# 7_esc.net
KiCad netlist of a schematic drawn in Altium Designer
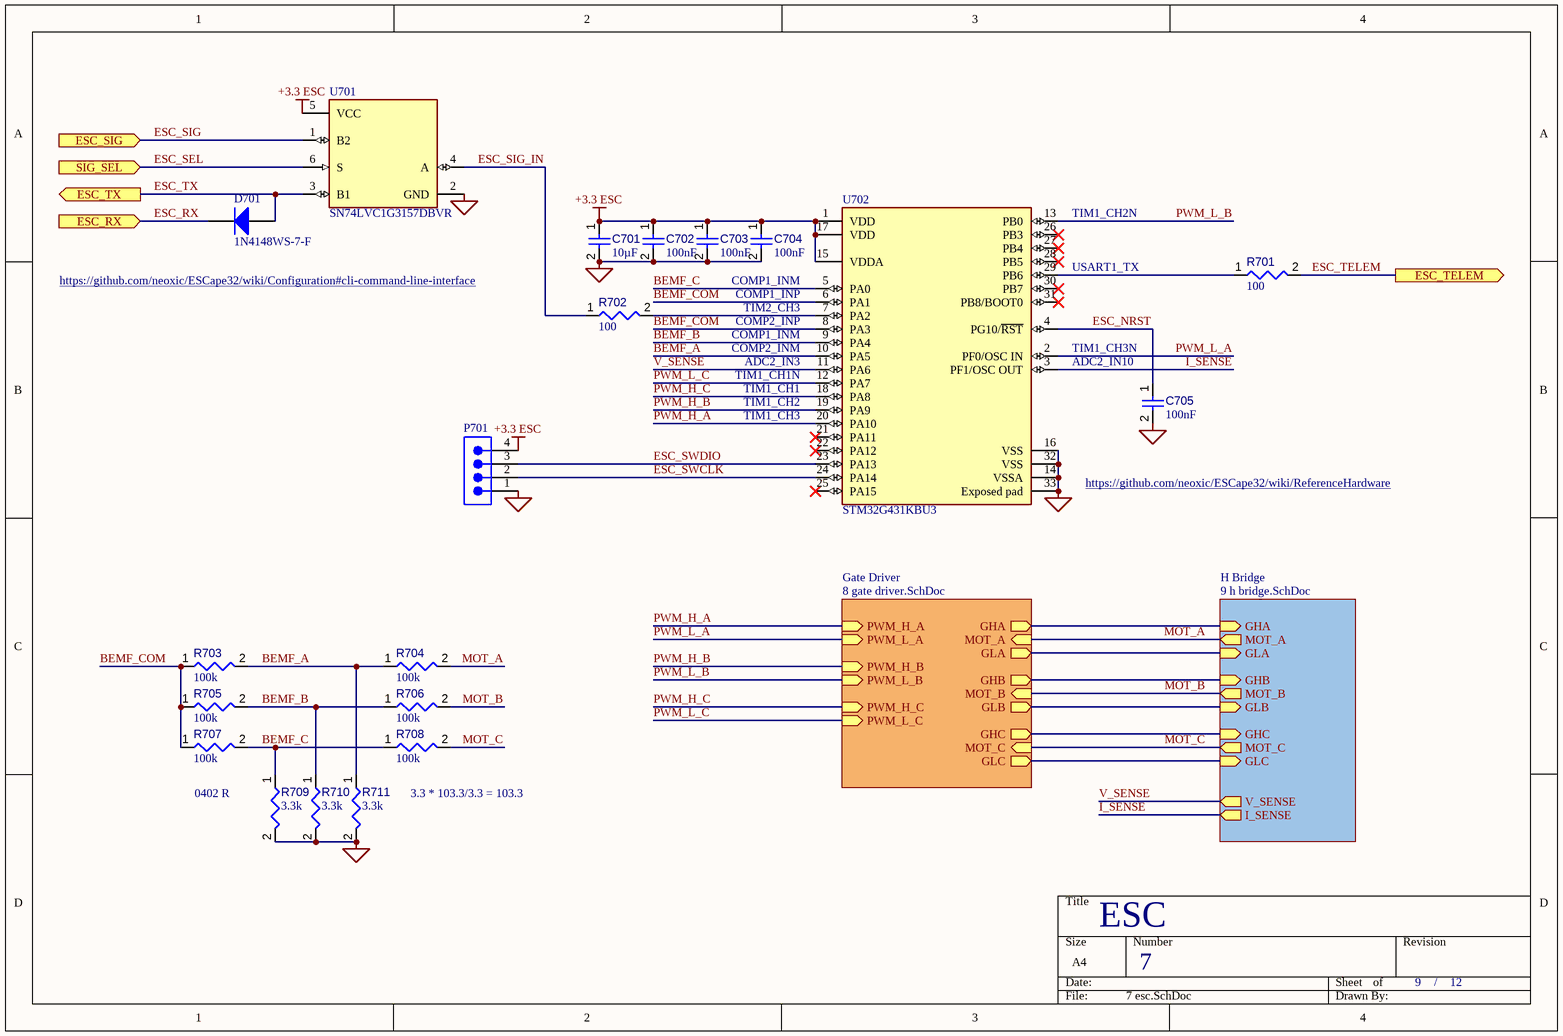
[diagram p0: 7 esc.SchDoc]

(export (version "E")
  (design (tool "Eeschema 10.0.6"))
  (components
    (comp (ref "C701")
      (value "10µF")
      (footprint "CAPC0603(1608)100_L")
      (description "Chip Capacitor, 10µF +/-20%, 10V, 0603, Thickness 1 mm")
      (fields (field (name "TOLERANCE") "10%") (field (name "Comment") "Capacitor 10µF +/-20% 10V 0603"))
      (libsource (lib "UBC Uncrewed Aircraft Systems") (part "CAP-NP-2"))
    )
    (comp (ref "C702")
      (value "100nF")
      (footprint "CAPC0402(1005)60_L")
      (description "Chip Capacitor, 100nF +/-20%, 25V, 0402, Thickness 0.6 mm")
      (fields (field (name "TOLERANCE") "10%") (field (name "Comment") "Capacitor 100nF +/-20% 25V 0402"))
      (libsource (lib "UBC Uncrewed Aircraft Systems") (part "CAP-NP-2"))
    )
    (comp (ref "C703")
      (value "100nF")
      (footprint "CAPC0402(1005)60_L")
      (description "Chip Capacitor, 100nF +/-20%, 25V, 0402, Thickness 0.6 mm")
      (fields (field (name "TOLERANCE") "10%") (field (name "Comment") "Capacitor 100nF +/-20% 25V 0402"))
      (libsource (lib "UBC Uncrewed Aircraft Systems") (part "CAP-NP-2"))
    )
    (comp (ref "C704")
      (value "100nF")
      (footprint "CAPC0402(1005)60_L")
      (description "Chip Capacitor, 100nF +/-20%, 25V, 0402, Thickness 0.6 mm")
      (fields (field (name "TOLERANCE") "10%") (field (name "Comment") "Capacitor 100nF +/-20% 25V 0402"))
      (libsource (lib "UBC Uncrewed Aircraft Systems") (part "CAP-NP-2"))
    )
    (comp (ref "C705")
      (value "100nF")
      (footprint "CAPC0402(1005)60_L")
      (description "Chip Capacitor, 100nF +/-20%, 25V, 0402, Thickness 0.6 mm")
      (fields (field (name "TOLERANCE") "10%") (field (name "Comment") "Capacitor 100nF +/-20% 25V 0402"))
      (libsource (lib "UBC Uncrewed Aircraft Systems") (part "CAP-NP-2"))
    )
    (comp (ref "D701")
      (value "1N4148WS-7-F")
      (footprint "DIOD-SOD323-2-A_V")
      (description "Fast Switching Diode, 75 V, 0.3 A, -65 to 150 degC, 2-Pin SOD323, RoHS, Tape and Reel")
      (libsource (lib "Altium Content Vault") (part "D-AK-2"))
    )
    (comp (ref "P701")
      (value "61300411121")
      (footprint "61300411121")
      (libsource (lib "Altium Content Vault") (part "Header_Male_1R_04P"))
    )
    (comp (ref "R701")
      (value "100")
      (footprint "RESC0402(1005)_L")
      (description "Chip Resistor, 100 Ohms, +/-1 %, 63 mW, -55 to 155 degC, 0402")
      (fields (field (name "POWER") "63mW") (field (name "TOLERANCE") "1%"))
      (libsource (lib "UBC Uncrewed Aircraft Systems") (part "RES-2"))
    )
    (comp (ref "R702")
      (value "100")
      (footprint "RESC0402(1005)_L")
      (description "Chip Resistor, 100 Ohms, +/-1 %, 63 mW, -55 to 155 degC, 0402")
      (fields (field (name "POWER") "63mW") (field (name "TOLERANCE") "1%"))
      (libsource (lib "UBC Uncrewed Aircraft Systems") (part "RES-2"))
    )
    (comp (ref "R703")
      (value "100k")
      (footprint "RESC0402(1005)_L")
      (description "Chip Resistor, 100 kOhms, +/-1 %, 63 mW, -55 to 155 degC, 0402")
      (fields (field (name "TOLERANCE") "1%") (field (name "POWER") "63mW"))
      (libsource (lib "UBC Uncrewed Aircraft Systems") (part "RES-2"))
    )
    (comp (ref "R704")
      (value "100k")
      (footprint "RESC0402(1005)_L")
      (description "Chip Resistor, 100 kOhms, +/-1 %, 63 mW, -55 to 155 degC, 0402")
      (fields (field (name "TOLERANCE") "1%") (field (name "POWER") "63mW"))
      (libsource (lib "UBC Uncrewed Aircraft Systems") (part "RES-2"))
    )
    (comp (ref "R705")
      (value "100k")
      (footprint "RESC0402(1005)_L")
      (description "Chip Resistor, 100 kOhms, +/-1 %, 63 mW, -55 to 155 degC, 0402")
      (fields (field (name "TOLERANCE") "1%") (field (name "POWER") "63mW"))
      (libsource (lib "UBC Uncrewed Aircraft Systems") (part "RES-2"))
    )
    (comp (ref "R706")
      (value "100k")
      (footprint "RESC0402(1005)_L")
      (description "Chip Resistor, 100 kOhms, +/-1 %, 63 mW, -55 to 155 degC, 0402")
      (fields (field (name "TOLERANCE") "1%") (field (name "POWER") "63mW"))
      (libsource (lib "UBC Uncrewed Aircraft Systems") (part "RES-2"))
    )
    (comp (ref "R707")
      (value "100k")
      (footprint "RESC0402(1005)_L")
      (description "Chip Resistor, 100 kOhms, +/-1 %, 63 mW, -55 to 155 degC, 0402")
      (fields (field (name "TOLERANCE") "1%") (field (name "POWER") "63mW"))
      (libsource (lib "UBC Uncrewed Aircraft Systems") (part "RES-2"))
    )
    (comp (ref "R708")
      (value "100k")
      (footprint "RESC0402(1005)_L")
      (description "Chip Resistor, 100 kOhms, +/-1 %, 63 mW, -55 to 155 degC, 0402")
      (fields (field (name "TOLERANCE") "1%") (field (name "POWER") "63mW"))
      (libsource (lib "UBC Uncrewed Aircraft Systems") (part "RES-2"))
    )
    (comp (ref "R709")
      (value "3.3k")
      (footprint "RESC0402(1005)_L")
      (description "Chip Resistor, 3.3 kOhms, +/-1 %, 63 mW, -55 to 155 degC, 0402")
      (fields (field (name "TOLERANCE") "1%") (field (name "POWER") "63mW"))
      (libsource (lib "UBC Uncrewed Aircraft Systems") (part "RES-2"))
    )
    (comp (ref "R710")
      (value "3.3k")
      (footprint "RESC0402(1005)_L")
      (description "Chip Resistor, 3.3 kOhms, +/-1 %, 63 mW, -55 to 155 degC, 0402")
      (fields (field (name "TOLERANCE") "1%") (field (name "POWER") "63mW"))
      (libsource (lib "UBC Uncrewed Aircraft Systems") (part "RES-2"))
    )
    (comp (ref "R711")
      (value "3.3k")
      (footprint "RESC0402(1005)_L")
      (description "Chip Resistor, 3.3 kOhms, +/-1 %, 63 mW, -55 to 155 degC, 0402")
      (fields (field (name "TOLERANCE") "1%") (field (name "POWER") "63mW"))
      (libsource (lib "UBC Uncrewed Aircraft Systems") (part "RES-2"))
    )
    (comp (ref "U701")
      (value "SN74LVC1G3157DBVR")
      (footprint "FP-DBV0006A-IPC_C")
      (description "IC SWITCH SPDT SOT23-6")
      (libsource (lib "Altium Content Vault") (part "14cfcf06f1431fbc89496e2a44d6624"))
    )
    (comp (ref "U702")
      (value "STM32G431KBU3")
      (footprint "FP-UFQFPN32-A0B8-MFG")
      (description "IC MCU 32BIT 128KB FLSH 32UFQFPN")
      (libsource (lib "Altium Content Vault") (part "b0f9ef315fadbc83d4ed39e8b05710e"))
    )
  )
  (nets
    (net (code "1") (name "+3.3 ESC") (class "Default")
      (node (ref "C701") (pin "1") (pinfunction "1_1") (pintype "passive"))
      (node (ref "C702") (pin "1") (pinfunction "1_1") (pintype "passive"))
      (node (ref "C703") (pin "1") (pinfunction "1_1") (pintype "passive"))
      (node (ref "C704") (pin "1") (pinfunction "1_1") (pintype "passive"))
      (node (ref "P701") (pin "4") (pinfunction "4_4") (pintype "passive"))
      (node (ref "U701") (pin "5") (pinfunction "VCC_5") (pintype "power_in"))
      (node (ref "U702") (pin "1") (pinfunction "VDD_1") (pintype "power_in"))
      (node (ref "U702") (pin "15") (pinfunction "VDDA_15") (pintype "power_in"))
      (node (ref "U702") (pin "17") (pinfunction "VDD_17") (pintype "power_in"))
    )
    (net (code "2") (name "/BEMF_A") (class "Default")
      (node (ref "R703") (pin "2") (pinfunction "2_2") (pintype "passive"))
      (node (ref "R704") (pin "1") (pinfunction "1_1") (pintype "passive"))
      (node (ref "R711") (pin "1") (pinfunction "1_1") (pintype "passive"))
      (node (ref "U702") (pin "10") (pinfunction "PA5_10") (pintype "bidirectional"))
    )
    (net (code "3") (name "/BEMF_B") (class "Default")
      (node (ref "R705") (pin "2") (pinfunction "2_2") (pintype "passive"))
      (node (ref "R706") (pin "1") (pinfunction "1_1") (pintype "passive"))
      (node (ref "R710") (pin "1") (pinfunction "1_1") (pintype "passive"))
      (node (ref "U702") (pin "9") (pinfunction "PA4_9") (pintype "bidirectional"))
    )
    (net (code "4") (name "/BEMF_C") (class "Default")
      (node (ref "R707") (pin "2") (pinfunction "2_2") (pintype "passive"))
      (node (ref "R708") (pin "1") (pinfunction "1_1") (pintype "passive"))
      (node (ref "R709") (pin "1") (pinfunction "1_1") (pintype "passive"))
      (node (ref "U702") (pin "5") (pinfunction "PA0_5") (pintype "bidirectional"))
    )
    (net (code "5") (name "/BEMF_COM") (class "Default")
      (node (ref "R703") (pin "1") (pinfunction "1_1") (pintype "passive"))
      (node (ref "R705") (pin "1") (pinfunction "1_1") (pintype "passive"))
      (node (ref "R707") (pin "1") (pinfunction "1_1") (pintype "passive"))
      (node (ref "U702") (pin "6") (pinfunction "PA1_6") (pintype "bidirectional"))
      (node (ref "U702") (pin "8") (pinfunction "PA3_8") (pintype "bidirectional"))
    )
    (net (code "6") (name "/ESC_NRST") (class "Default")
      (node (ref "C705") (pin "1") (pinfunction "1_1") (pintype "passive"))
      (node (ref "U702") (pin "4") (pinfunction "PG10/~{RST}_4") (pintype "bidirectional"))
    )
    (net (code "7") (name "/ESC_RX") (class "Default")
      (node (ref "D701") (pin "2") (pinfunction "K_2") (pintype "passive"))
    )
    (net (code "8") (name "/ESC_SEL") (class "Default")
      (node (ref "U701") (pin "6") (pinfunction "S_6") (pintype "input"))
    )
    (net (code "9") (name "/ESC_SIG") (class "Default")
      (node (ref "U701") (pin "1") (pinfunction "B2_1") (pintype "bidirectional"))
    )
    (net (code "10") (name "/ESC_SIG_IN") (class "Default")
      (node (ref "R702") (pin "1") (pinfunction "1_1") (pintype "passive"))
      (node (ref "U701") (pin "4") (pinfunction "A_4") (pintype "bidirectional"))
    )
    (net (code "11") (name "/ESC_SWCLK") (class "Default")
      (node (ref "P701") (pin "2") (pinfunction "2_2") (pintype "passive"))
      (node (ref "U702") (pin "24") (pinfunction "PA14_24") (pintype "bidirectional"))
    )
    (net (code "12") (name "/ESC_SWDIO") (class "Default")
      (node (ref "P701") (pin "3") (pinfunction "3_3") (pintype "passive"))
      (node (ref "U702") (pin "23") (pinfunction "PA13_23") (pintype "bidirectional"))
    )
    (net (code "13") (name "/ESC_TELEM") (class "Default")
      (node (ref "R701") (pin "2") (pinfunction "2_2") (pintype "passive"))
    )
    (net (code "14") (name "/ESC_TX") (class "Default")
      (node (ref "D701") (pin "1") (pinfunction "A_1") (pintype "passive"))
      (node (ref "U701") (pin "3") (pinfunction "B1_3") (pintype "bidirectional"))
    )
    (net (code "21") (name "/I_SENSE") (class "Default")
      (node (ref "U702") (pin "3") (pinfunction "PF1/OSC_OUT_3") (pintype "bidirectional"))
    )
    (net (code "22") (name "/MOT_A") (class "Default")
      (node (ref "R704") (pin "2") (pinfunction "2_2") (pintype "passive"))
    )
    (net (code "23") (name "/MOT_B") (class "Default")
      (node (ref "R706") (pin "2") (pinfunction "2_2") (pintype "passive"))
    )
    (net (code "24") (name "/MOT_C") (class "Default")
      (node (ref "R708") (pin "2") (pinfunction "2_2") (pintype "passive"))
    )
    (net (code "25") (name "/PWM_H_A") (class "Default")
      (node (ref "U702") (pin "20") (pinfunction "PA10_20") (pintype "bidirectional"))
    )
    (net (code "26") (name "/PWM_H_B") (class "Default")
      (node (ref "U702") (pin "19") (pinfunction "PA9_19") (pintype "bidirectional"))
    )
    (net (code "27") (name "/PWM_H_C") (class "Default")
      (node (ref "U702") (pin "18") (pinfunction "PA8_18") (pintype "bidirectional"))
    )
    (net (code "28") (name "/PWM_L_A") (class "Default")
      (node (ref "U702") (pin "2") (pinfunction "PF0/OSC_IN_2") (pintype "bidirectional"))
    )
    (net (code "29") (name "/PWM_L_B") (class "Default")
      (node (ref "U702") (pin "13") (pinfunction "PB0_13") (pintype "bidirectional"))
    )
    (net (code "30") (name "/PWM_L_C") (class "Default")
      (node (ref "U702") (pin "12") (pinfunction "PA7_12") (pintype "bidirectional"))
    )
    (net (code "31") (name "/V_SENSE") (class "Default")
      (node (ref "U702") (pin "11") (pinfunction "PA6_11") (pintype "bidirectional"))
    )
    (net (code "32") (name "Net-(U702-PA2)") (class "Default")
      (node (ref "R702") (pin "2") (pinfunction "2_2") (pintype "passive"))
      (node (ref "U702") (pin "7") (pinfunction "PA2_7") (pintype "bidirectional"))
    )
    (net (code "33") (name "Net-(U702-PB6)") (class "Default")
      (node (ref "R701") (pin "1") (pinfunction "1_1") (pintype "passive"))
      (node (ref "U702") (pin "29") (pinfunction "PB6_29") (pintype "bidirectional"))
    )
    (net (code "34") (name "PGND") (class "Default")
      (node (ref "C701") (pin "2") (pinfunction "2_2") (pintype "passive"))
      (node (ref "C702") (pin "2") (pinfunction "2_2") (pintype "passive"))
      (node (ref "C703") (pin "2") (pinfunction "2_2") (pintype "passive"))
      (node (ref "C704") (pin "2") (pinfunction "2_2") (pintype "passive"))
      (node (ref "C705") (pin "2") (pinfunction "2_2") (pintype "passive"))
      (node (ref "P701") (pin "1") (pinfunction "1_1") (pintype "passive"))
      (node (ref "R709") (pin "2") (pinfunction "2_2") (pintype "passive"))
      (node (ref "R710") (pin "2") (pinfunction "2_2") (pintype "passive"))
      (node (ref "R711") (pin "2") (pinfunction "2_2") (pintype "passive"))
      (node (ref "U701") (pin "2") (pinfunction "GND_2") (pintype "power_in"))
      (node (ref "U702") (pin "14") (pinfunction "VSSA_14") (pintype "power_in"))
      (node (ref "U702") (pin "16") (pinfunction "VSS_16") (pintype "power_in"))
      (node (ref "U702") (pin "32") (pinfunction "VSS_32") (pintype "power_in"))
      (node (ref "U702") (pin "33") (pinfunction "Exposed_pad_33") (pintype "power_in"))
    )
    (net (code "35") (name "unconnected-(U702-PA11-Pad21)") (class "Default")
      (node (ref "U702") (pin "21") (pinfunction "PA11_21") (pintype "bidirectional+no_connect"))
    )
    (net (code "36") (name "unconnected-(U702-PA12-Pad22)") (class "Default")
      (node (ref "U702") (pin "22") (pinfunction "PA12_22") (pintype "bidirectional+no_connect"))
    )
    (net (code "37") (name "unconnected-(U702-PA15-Pad25)") (class "Default")
      (node (ref "U702") (pin "25") (pinfunction "PA15_25") (pintype "bidirectional+no_connect"))
    )
    (net (code "38") (name "unconnected-(U702-PB3-Pad26)") (class "Default")
      (node (ref "U702") (pin "26") (pinfunction "PB3_26") (pintype "bidirectional+no_connect"))
    )
    (net (code "39") (name "unconnected-(U702-PB4-Pad27)") (class "Default")
      (node (ref "U702") (pin "27") (pinfunction "PB4_27") (pintype "bidirectional+no_connect"))
    )
    (net (code "40") (name "unconnected-(U702-PB5-Pad28)") (class "Default")
      (node (ref "U702") (pin "28") (pinfunction "PB5_28") (pintype "bidirectional+no_connect"))
    )
    (net (code "41") (name "unconnected-(U702-PB7-Pad30)") (class "Default")
      (node (ref "U702") (pin "30") (pinfunction "PB7_30") (pintype "bidirectional+no_connect"))
    )
    (net (code "42") (name "unconnected-(U702-PB8{slash}BOOT0-Pad31)") (class "Default")
      (node (ref "U702") (pin "31") (pinfunction "PB8/BOOT0_31") (pintype "bidirectional+no_connect"))
    )
  )
)
